# FTDI_SmartBasic.net
KiCad netlist of a schematic drawn in EAGLE
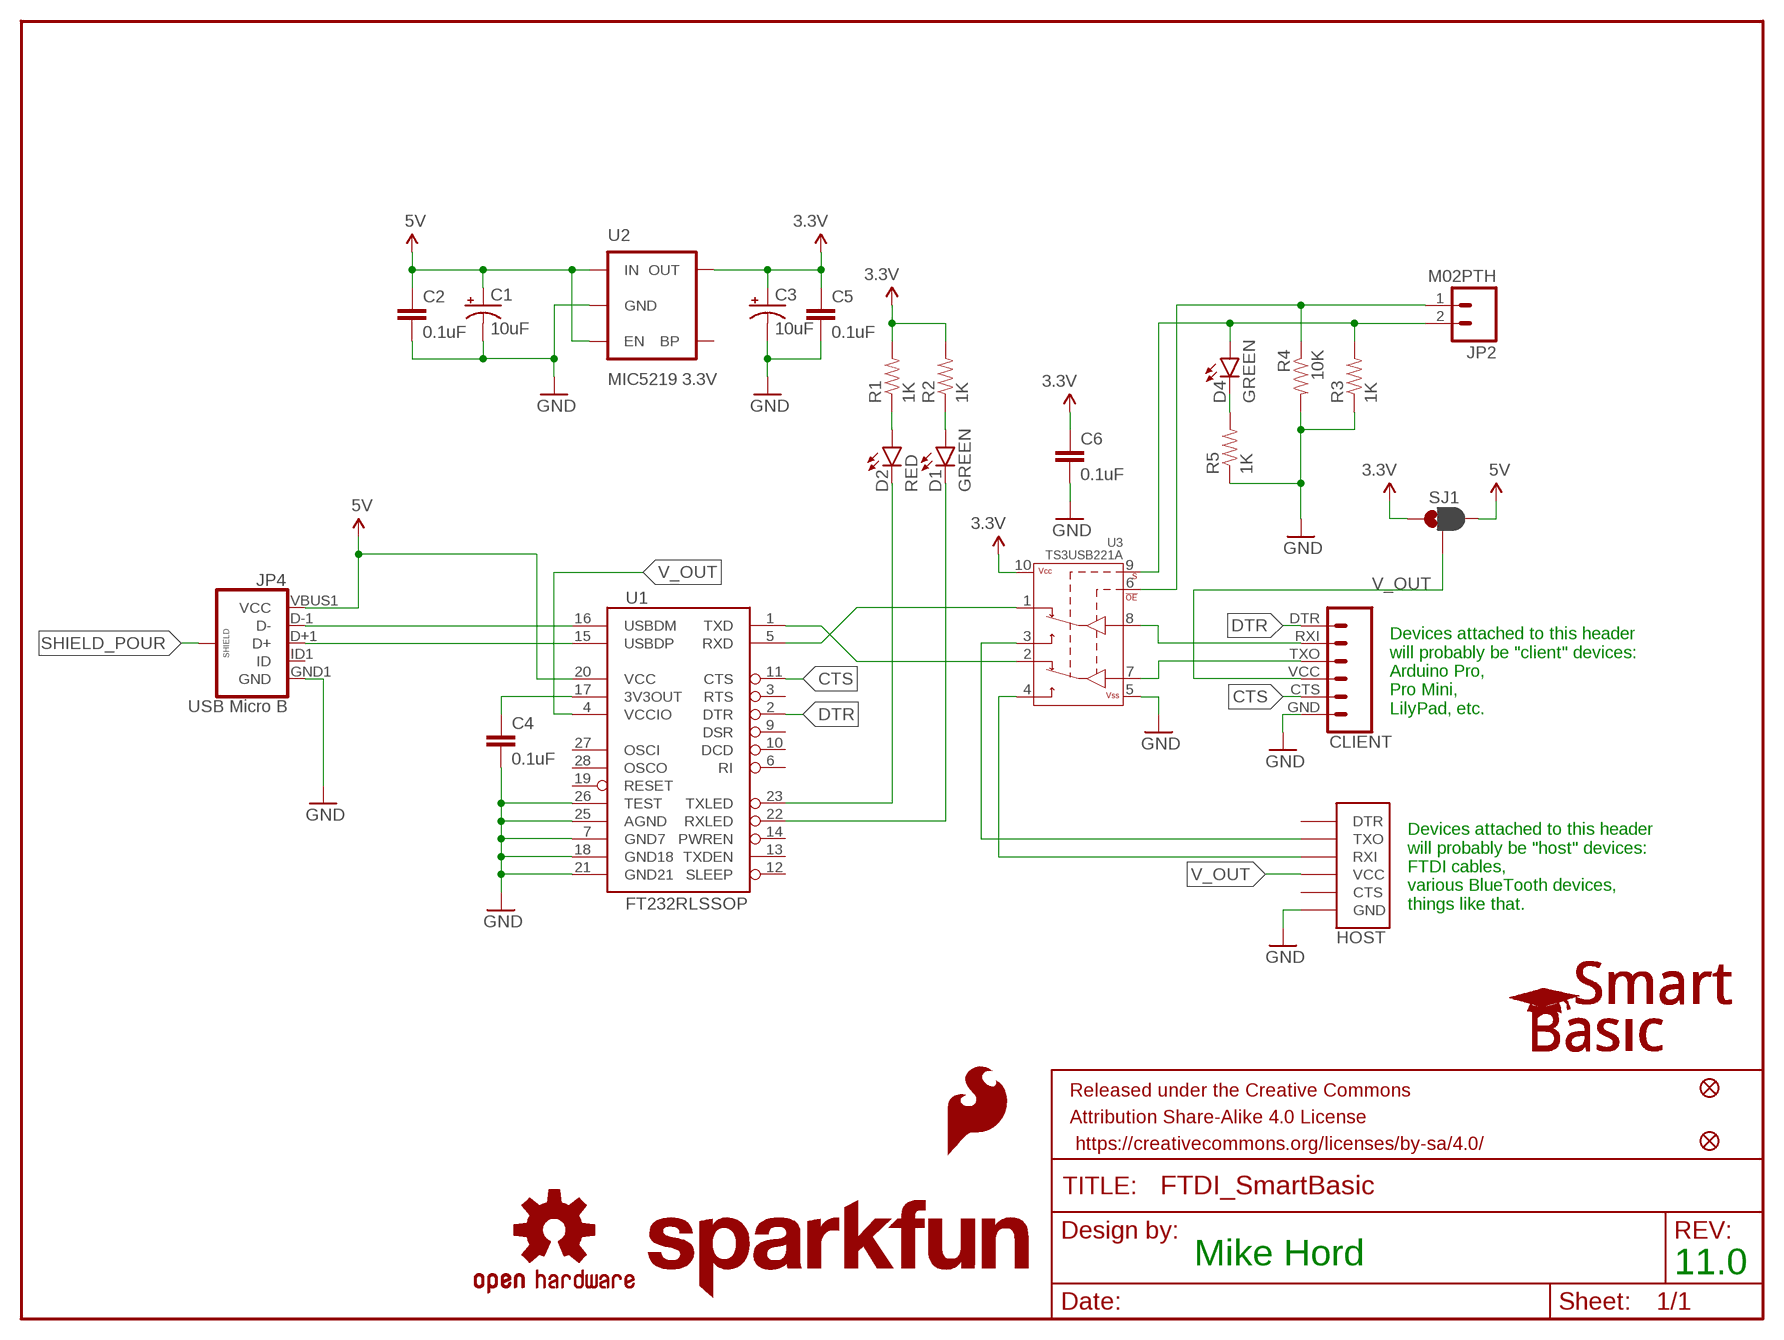
[diagram p0: schematic, sheet 1]

(export (version "E")
  (design (tool "Eeschema 10.0.6"))
  (components
    (comp (ref "C1")
      (value "10uF")
      (footprint "eagle-import:EIA3216")
      (libsource (lib "eagle-import") (part "10UF-16V-10%(TANT)"))
    )
    (comp (ref "C2")
      (value "0.1uF")
      (footprint "eagle-import:0603-CAP")
      (libsource (lib "eagle-import") (part "0.1UF-25V(+80/-20%)(0603)"))
    )
    (comp (ref "C3")
      (value "10uF")
      (footprint "eagle-import:EIA3216")
      (libsource (lib "eagle-import") (part "10UF-16V-10%(TANT)"))
    )
    (comp (ref "C4")
      (value "0.1uF")
      (footprint "eagle-import:0603-CAP")
      (libsource (lib "eagle-import") (part "0.1UF-25V(+80/-20%)(0603)"))
    )
    (comp (ref "C5")
      (value "0.1uF")
      (footprint "eagle-import:0603-CAP")
      (libsource (lib "eagle-import") (part "0.1UF-25V(+80/-20%)(0603)"))
    )
    (comp (ref "C6")
      (value "0.1uF")
      (footprint "eagle-import:0603-CAP")
      (libsource (lib "eagle-import") (part "0.1UF-25V(+80/-20%)(0603)"))
    )
    (comp (ref "CLIENT")
      (value "FTDI_BASICPTH")
      (footprint "eagle-import:FTDI_BASIC")
      (libsource (lib "eagle-import") (part "FTDI_BASICPTH"))
    )
    (comp (ref "D1")
      (value "GREEN")
      (footprint "eagle-import:LED-0603")
      (libsource (lib "eagle-import") (part "LED-GREEN0603"))
    )
    (comp (ref "D2")
      (value "RED")
      (footprint "eagle-import:LED-0603")
      (libsource (lib "eagle-import") (part "LED-RED0603"))
    )
    (comp (ref "D4")
      (value "GREEN")
      (footprint "eagle-import:LED-0603")
      (libsource (lib "eagle-import") (part "LED-GREEN0603"))
    )
    (comp (ref "FID1")
      (value "FIDUCIAL1X2")
      (footprint "eagle-import:FIDUCIAL-1X2")
      (libsource (lib "eagle-import") (part "FIDUCIAL1X2"))
    )
    (comp (ref "FID2")
      (value "FIDUCIAL1X2")
      (footprint "eagle-import:FIDUCIAL-1X2")
      (libsource (lib "eagle-import") (part "FIDUCIAL1X2"))
    )
    (comp (ref "FRAME1")
      (value "FRAME-LETTER")
      (footprint "eagle-import:CREATIVE_COMMONS")
      (libsource (lib "eagle-import") (part "FRAME-LETTER"))
    )
    (comp (ref "HOST")
      (value "FTDI_DEVICE")
      (footprint "eagle-import:FTDI_DEVICE_SIDE")
      (libsource (lib "eagle-import") (part "FTDI_DEVICE"))
    )
    (comp (ref "JP2")
      (value "M02PTH")
      (footprint "eagle-import:1X02")
      (libsource (lib "eagle-import") (part "M02PTH"))
    )
    (comp (ref "JP4")
      (value "USB Micro B")
      (footprint "eagle-import:USB-B-MICRO-SMD_V03")
      (libsource (lib "eagle-import") (part "USB_MICROB_PLUGCONN-11752"))
    )
    (comp (ref "LOGO1")
      (value "SFE_LOGO_NAME.1_INCH")
      (footprint "eagle-import:SFE_LOGO_NAME_.1")
      (libsource (lib "eagle-import") (part "SFE_LOGO_NAME.1_INCH"))
    )
    (comp (ref "LOGO2")
      (value "SFE_LOGO_FLAME.2_INCH")
      (footprint "eagle-import:SFE_LOGO_FLAME_.2")
      (libsource (lib "eagle-import") (part "SFE_LOGO_FLAME.2_INCH"))
    )
    (comp (ref "LOGO3")
      (value "OSHW-LOGOS")
      (footprint "eagle-import:OSHW-LOGO-S")
      (libsource (lib "eagle-import") (part "OSHW-LOGOS"))
    )
    (comp (ref "R1")
      (value "1K")
      (footprint "eagle-import:0603-RES")
      (libsource (lib "eagle-import") (part "1KOHM1/10W1%(0603)"))
    )
    (comp (ref "R2")
      (value "1K")
      (footprint "eagle-import:0603-RES")
      (libsource (lib "eagle-import") (part "1KOHM1/10W1%(0603)"))
    )
    (comp (ref "R3")
      (value "1K")
      (footprint "eagle-import:0603-RES")
      (libsource (lib "eagle-import") (part "1KOHM1/10W1%(0603)"))
    )
    (comp (ref "R4")
      (value "10K")
      (footprint "eagle-import:0603-RES")
      (libsource (lib "eagle-import") (part "10KOHM1/10W1%(0603)0603"))
    )
    (comp (ref "R5")
      (value "1K")
      (footprint "eagle-import:0603-RES")
      (libsource (lib "eagle-import") (part "1KOHM1/10W1%(0603)"))
    )
    (comp (ref "SJ1")
      (value "JUMPER-PAD-3-2OF3_NC_BY_PASTE")
      (footprint "eagle-import:PAD-JUMPER-3-2OF3_NC_BY_PASTE_YES_SILK_FULL_BOX")
      (libsource (lib "eagle-import") (part "JUMPER-PAD-3-2OF3_NC_BY_PASTE"))
    )
    (comp (ref "U$1")
      (value "SMART_BASIC_LOGO")
      (footprint "eagle-import:SMART_BASIC_LOGO")
      (libsource (lib "eagle-import") (part "SMART_BASIC_LOGO"))
    )
    (comp (ref "U1")
      (value "FT232RLSSOP")
      (footprint "eagle-import:SSOP28DB")
      (libsource (lib "eagle-import") (part "FT232RLSSOP"))
    )
    (comp (ref "U2")
      (value "MIC5219 3.3V")
      (footprint "eagle-import:SOT23-5")
      (libsource (lib "eagle-import") (part "V_REG_MIC52193.3V"))
    )
    (comp (ref "U3")
      (value "TS3USB221A")
      (footprint "eagle-import:QFN-10-RSE")
      (libsource (lib "eagle-import") (part "TS3USB221A"))
    )
  )
  (nets
    (net (code "1") (name "3.3V") (class "Default")
      (node (ref "C3") (pin "A") (pinfunction "+_A") (pintype "passive"))
      (node (ref "C5") (pin "1") (pinfunction "1_1") (pintype "passive"))
      (node (ref "C6") (pin "1") (pinfunction "1_1") (pintype "passive"))
      (node (ref "R1") (pin "2") (pinfunction "2_2") (pintype "passive"))
      (node (ref "R2") (pin "2") (pinfunction "2_2") (pintype "passive"))
      (node (ref "SJ1") (pin "1") (pinfunction "1_1") (pintype "passive"))
      (node (ref "U2") (pin "5") (pinfunction "OUT_5") (pintype "passive"))
      (node (ref "U3") (pin "10") (pinfunction "VCC_10") (pintype "bidirectional"))
    )
    (net (code "2") (name "5V") (class "Default")
      (node (ref "C1") (pin "A") (pinfunction "+_A") (pintype "passive"))
      (node (ref "C2") (pin "1") (pinfunction "1_1") (pintype "passive"))
      (node (ref "JP4") (pin "VBUS1") (pinfunction "VCC_VBUS1") (pintype "bidirectional"))
      (node (ref "SJ1") (pin "3") (pinfunction "3_3") (pintype "passive"))
      (node (ref "U1") (pin "20") (pinfunction "VCC_20") (pintype "power_in"))
      (node (ref "U2") (pin "1") (pinfunction "IN_1") (pintype "input"))
      (node (ref "U2") (pin "3") (pinfunction "EN_3") (pintype "input"))
    )
    (net (code "3") (name "CTS") (class "Default")
      (node (ref "CLIENT") (pin "CTS") (pinfunction "5_CTS") (pintype "passive"))
      (node (ref "U1") (pin "11") (pinfunction "CTS_11") (pintype "input"))
    )
    (net (code "4") (name "DTR") (class "Default")
      (node (ref "CLIENT") (pin "DTR") (pinfunction "1_DTR") (pintype "passive"))
      (node (ref "U1") (pin "2") (pinfunction "DTR_2") (pintype "output"))
    )
    (net (code "5") (name "GND") (class "Default")
      (node (ref "C1") (pin "C") (pinfunction "-_C") (pintype "passive"))
      (node (ref "C2") (pin "2") (pinfunction "2_2") (pintype "passive"))
      (node (ref "C3") (pin "C") (pinfunction "-_C") (pintype "passive"))
      (node (ref "C4") (pin "2") (pinfunction "2_2") (pintype "passive"))
      (node (ref "C5") (pin "2") (pinfunction "2_2") (pintype "passive"))
      (node (ref "C6") (pin "2") (pinfunction "2_2") (pintype "passive"))
      (node (ref "CLIENT") (pin "GND") (pinfunction "6_GND") (pintype "passive"))
      (node (ref "HOST") (pin "P$6") (pinfunction "GND_P$6") (pintype "bidirectional"))
      (node (ref "JP4") (pin "GND1") (pinfunction "GND_GND1") (pintype "bidirectional"))
      (node (ref "R3") (pin "1") (pinfunction "1_1") (pintype "passive"))
      (node (ref "R4") (pin "2") (pinfunction "2_2") (pintype "passive"))
      (node (ref "R5") (pin "1") (pinfunction "1_1") (pintype "passive"))
      (node (ref "U1") (pin "18") (pinfunction "GND18_18") (pintype "power_in"))
      (node (ref "U1") (pin "21") (pinfunction "GND21_21") (pintype "power_in"))
      (node (ref "U1") (pin "25") (pinfunction "AGND_25") (pintype "power_in"))
      (node (ref "U1") (pin "26") (pinfunction "TEST_26") (pintype "input"))
      (node (ref "U1") (pin "7") (pinfunction "GND7_7") (pintype "power_in"))
      (node (ref "U2") (pin "2") (pinfunction "GND_2") (pintype "input"))
      (node (ref "U3") (pin "5") (pinfunction "VSS_5") (pintype "bidirectional"))
    )
    (net (code "6") (name "Net-(CLIENT-2)") (class "Default")
      (node (ref "CLIENT") (pin "RXI") (pinfunction "2_RXI") (pintype "passive"))
      (node (ref "U3") (pin "8") (pinfunction "D+_8") (pintype "bidirectional"))
    )
    (net (code "7") (name "Net-(CLIENT-3)") (class "Default")
      (node (ref "CLIENT") (pin "TXO") (pinfunction "3_TXO") (pintype "passive"))
      (node (ref "U3") (pin "7") (pinfunction "D-_7") (pintype "bidirectional"))
    )
    (net (code "8") (name "Net-(D1-PadA)") (class "Default")
      (node (ref "D1") (pin "A") (pinfunction "A_A") (pintype "passive"))
      (node (ref "R2") (pin "1") (pinfunction "1_1") (pintype "passive"))
    )
    (net (code "9") (name "Net-(D2-PadA)") (class "Default")
      (node (ref "D2") (pin "A") (pinfunction "A_A") (pintype "passive"))
      (node (ref "R1") (pin "1") (pinfunction "1_1") (pintype "passive"))
    )
    (net (code "10") (name "Net-(D4-PadC)") (class "Default")
      (node (ref "D4") (pin "C") (pinfunction "C_C") (pintype "passive"))
      (node (ref "R5") (pin "2") (pinfunction "2_2") (pintype "passive"))
    )
    (net (code "11") (name "Net-(HOST-RXI)") (class "Default")
      (node (ref "HOST") (pin "P$3") (pinfunction "RXI_P$3") (pintype "bidirectional"))
      (node (ref "U3") (pin "4") (pinfunction "2D-_4") (pintype "bidirectional"))
    )
    (net (code "12") (name "Net-(HOST-TXO)") (class "Default")
      (node (ref "HOST") (pin "P$2") (pinfunction "TXO_P$2") (pintype "bidirectional"))
      (node (ref "U3") (pin "3") (pinfunction "2D+_3") (pintype "bidirectional"))
    )
    (net (code "13") (name "Net-(JP4-D+)") (class "Default")
      (node (ref "JP4") (pin "D+1") (pinfunction "D+_D+1") (pintype "bidirectional"))
      (node (ref "U1") (pin "15") (pinfunction "USBDP_15") (pintype "bidirectional"))
    )
    (net (code "14") (name "Net-(JP4-D-)") (class "Default")
      (node (ref "JP4") (pin "D-1") (pinfunction "D-_D-1") (pintype "bidirectional"))
      (node (ref "U1") (pin "16") (pinfunction "USBDM_16") (pintype "bidirectional"))
    )
    (net (code "15") (name "Net-(U1-3V3OUT)") (class "Default")
      (node (ref "C4") (pin "1") (pinfunction "1_1") (pintype "passive"))
      (node (ref "U1") (pin "17") (pinfunction "3V3OUT_17") (pintype "output"))
    )
    (net (code "16") (name "Net-(U1-RXD)") (class "Default")
      (node (ref "U1") (pin "5") (pinfunction "RXD_5") (pintype "input"))
      (node (ref "U3") (pin "1") (pinfunction "1D+_1") (pintype "bidirectional"))
    )
    (net (code "17") (name "Net-(U1-RXLED)") (class "Default")
      (node (ref "D1") (pin "C") (pinfunction "C_C") (pintype "passive"))
      (node (ref "U1") (pin "22") (pinfunction "RXLED_22") (pintype "input"))
    )
    (net (code "18") (name "Net-(U1-TXD)") (class "Default")
      (node (ref "U1") (pin "1") (pinfunction "TXD_1") (pintype "output"))
      (node (ref "U3") (pin "2") (pinfunction "1D-_2") (pintype "bidirectional"))
    )
    (net (code "19") (name "Net-(U1-TXLED)") (class "Default")
      (node (ref "D2") (pin "C") (pinfunction "C_C") (pintype "passive"))
      (node (ref "U1") (pin "23") (pinfunction "TXLED_23") (pintype "input"))
    )
    (net (code "20") (name "Net-(U3-S)") (class "Default")
      (node (ref "D4") (pin "A") (pinfunction "A_A") (pintype "passive"))
      (node (ref "JP2") (pin "2") (pinfunction "2_2") (pintype "passive"))
      (node (ref "R3") (pin "2") (pinfunction "2_2") (pintype "passive"))
      (node (ref "U3") (pin "9") (pinfunction "S_9") (pintype "bidirectional"))
    )
    (net (code "21") (name "Net-(U3-~{OE})") (class "Default")
      (node (ref "JP2") (pin "1") (pinfunction "1_1") (pintype "passive"))
      (node (ref "R4") (pin "1") (pinfunction "1_1") (pintype "passive"))
      (node (ref "U3") (pin "6") (pinfunction "~{OE}_6") (pintype "bidirectional"))
    )
    (net (code "22") (name "SHIELD_POUR") (class "Default")
      (node (ref "JP4") (pin "SHIELD1") (pinfunction "SHIELD_SHIELD1") (pintype "bidirectional"))
      (node (ref "JP4") (pin "SHIELD2") (pinfunction "SHIELD_SHIELD2") (pintype "bidirectional"))
      (node (ref "JP4") (pin "SHIELD3") (pinfunction "SHIELD_SHIELD3") (pintype "bidirectional"))
    )
    (net (code "23") (name "V_OUT") (class "Default")
      (node (ref "CLIENT") (pin "VCC") (pinfunction "4_VCC") (pintype "passive"))
      (node (ref "HOST") (pin "P$4") (pinfunction "VCC_P$4") (pintype "bidirectional"))
      (node (ref "SJ1") (pin "2") (pinfunction "2_2") (pintype "passive"))
      (node (ref "U1") (pin "4") (pinfunction "VCCIO_4") (pintype "power_in"))
    )
    (net (code "24") (name "unconnected-(HOST-CTS-PadP$5)") (class "Default")
      (node (ref "HOST") (pin "P$5") (pinfunction "CTS_P$5") (pintype "bidirectional"))
    )
    (net (code "25") (name "unconnected-(HOST-DTR-PadP$1)") (class "Default")
      (node (ref "HOST") (pin "P$1") (pinfunction "DTR_P$1") (pintype "bidirectional"))
    )
    (net (code "26") (name "unconnected-(JP4-ID-PadID1)") (class "Default")
      (node (ref "JP4") (pin "ID1") (pinfunction "ID_ID1") (pintype "bidirectional"))
    )
    (net (code "27") (name "unconnected-(U1-DCD-Pad10)") (class "Default")
      (node (ref "U1") (pin "10") (pinfunction "DCD_10") (pintype "input"))
    )
    (net (code "28") (name "unconnected-(U1-DSR-Pad9)") (class "Default")
      (node (ref "U1") (pin "9") (pinfunction "DSR_9") (pintype "input"))
    )
    (net (code "29") (name "unconnected-(U1-OSCI-Pad27)") (class "Default")
      (node (ref "U1") (pin "27") (pinfunction "OSCI_27") (pintype "input"))
    )
    (net (code "30") (name "unconnected-(U1-OSCO-Pad28)") (class "Default")
      (node (ref "U1") (pin "28") (pinfunction "OSCO_28") (pintype "output"))
    )
    (net (code "31") (name "unconnected-(U1-PWREN-Pad14)") (class "Default")
      (node (ref "U1") (pin "14") (pinfunction "PWREN_14") (pintype "input"))
    )
    (net (code "32") (name "unconnected-(U1-RESET-Pad19)") (class "Default")
      (node (ref "U1") (pin "19") (pinfunction "RESET_19") (pintype "input"))
    )
    (net (code "33") (name "unconnected-(U1-RI-Pad6)") (class "Default")
      (node (ref "U1") (pin "6") (pinfunction "RI_6") (pintype "input"))
    )
    (net (code "34") (name "unconnected-(U1-RTS-Pad3)") (class "Default")
      (node (ref "U1") (pin "3") (pinfunction "RTS_3") (pintype "output"))
    )
    (net (code "35") (name "unconnected-(U1-SLEEP-Pad12)") (class "Default")
      (node (ref "U1") (pin "12") (pinfunction "SLEEP_12") (pintype "input"))
    )
    (net (code "36") (name "unconnected-(U1-TXDEN-Pad13)") (class "Default")
      (node (ref "U1") (pin "13") (pinfunction "TXDEN_13") (pintype "input"))
    )
    (net (code "37") (name "unconnected-(U2-BP-Pad4)") (class "Default")
      (node (ref "U2") (pin "4") (pinfunction "BP_4") (pintype "input"))
    )
  )
)
